# Headphone_Filter.net
KiCad netlist of a schematic drawn in Altium Designer
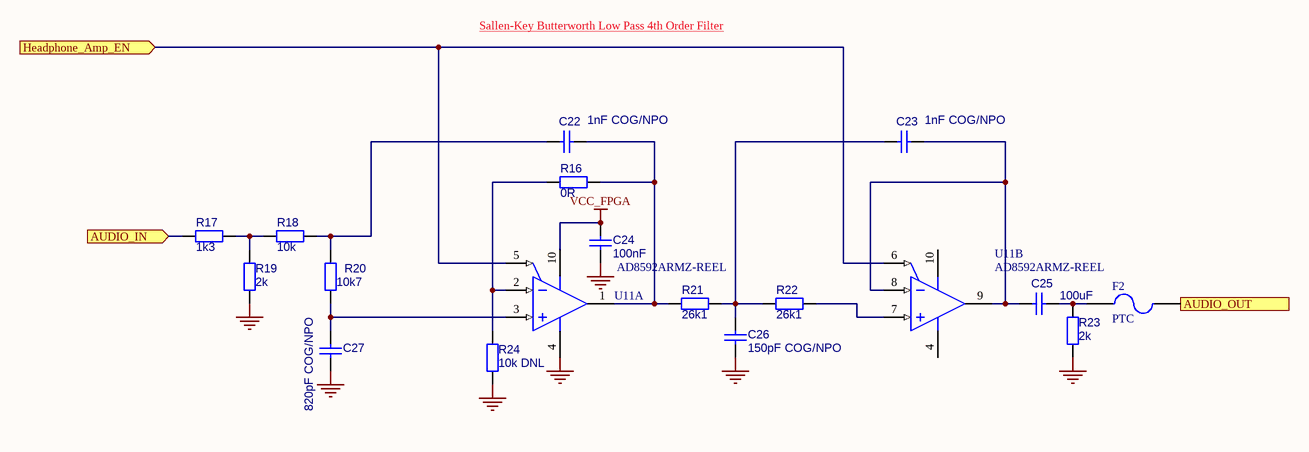
[diagram p0: Headphone Filter.SchDoc]

(export (version "E")
  (design (tool "Eeschema 10.0.6"))
  (components
    (comp (ref "C22")
      (value "1nF COG/NPO")
      (footprint "0603_CAP PF HD")
      (description "Capacitor")
      (fields (field (name "MANUFACTURER") "Wurth Electronics Inc."))
      (libsource (lib "Workshop Library 2010_06_24") (part "Cap"))
    )
    (comp (ref "C23")
      (value "1nF COG/NPO")
      (footprint "0603_CAP PF HD")
      (description "Capacitor")
      (fields (field (name "MANUFACTURER") "Wurth Electronics Inc."))
      (libsource (lib "Workshop Library 2010_06_24") (part "Cap"))
    )
    (comp (ref "C24")
      (value "100nF")
      (footprint "0603_CAP UF HD")
      (description "Capacitor")
      (libsource (lib "Workshop Library 2010_06_24") (part "Cap"))
    )
    (comp (ref "C25")
      (value "100uF")
      (footprint "1210-CAPACITOR UF")
      (description "Capacitor")
      (fields (field (name "MANUFACTURER") "Taiyo Yuden"))
      (libsource (lib "Workshop Library 2010_06_24") (part "Cap"))
    )
    (comp (ref "C26")
      (value "150pF COG/NPO")
      (footprint "0603_CAP PF HD")
      (description "Capacitor")
      (libsource (lib "Workshop Library 2010_06_24") (part "Cap"))
    )
    (comp (ref "C27")
      (value "820pF COG/NPO")
      (footprint "0603_CAP PF HD")
      (description "Capacitor")
      (libsource (lib "Workshop Library 2010_06_24") (part "Cap"))
    )
    (comp (ref "F2")
      (value "PTC")
      (footprint "0603-RESISTOR HD")
      (description "Fuse")
      (fields (field (name "MANUFACTURER") "Murata Electronics"))
      (libsource (lib "Workshop Library 2010_06_24") (part "Fuse"))
    )
    (comp (ref "R16")
      (value "0R")
      (footprint "0603-RESISTOR HD")
      (description "Resistor")
      (libsource (lib "") (part "Resistor_1"))
    )
    (comp (ref "R17")
      (value "1k3")
      (footprint "0603-RESISTOR HD")
      (description "Resistor")
      (libsource (lib "") (part "Resistor_1"))
    )
    (comp (ref "R18")
      (value "10k")
      (footprint "0603-RESISTOR HD")
      (description "Resistor")
      (libsource (lib "") (part "Resistor_2"))
    )
    (comp (ref "R19")
      (value "2k")
      (footprint "0603-RESISTOR HD")
      (description "Resistor")
      (libsource (lib "") (part "Resistor_3"))
    )
    (comp (ref "R20")
      (value "10k7")
      (footprint "0603-RESISTOR HD")
      (description "Resistor")
      (libsource (lib "Workshop Library 2010_06_24") (part "Resistor"))
    )
    (comp (ref "R21")
      (value "26k1")
      (footprint "0603-RESISTOR HD")
      (description "Resistor")
      (libsource (lib "") (part "Resistor_1"))
    )
    (comp (ref "R22")
      (value "26k1")
      (footprint "0603-RESISTOR HD")
      (description "Resistor")
      (libsource (lib "") (part "Resistor_2"))
    )
    (comp (ref "R23")
      (value "2k")
      (footprint "0603-RESISTOR HD")
      (description "Resistor")
      (libsource (lib "") (part "Resistor_3"))
    )
    (comp (ref "R24")
      (value "10k DNL")
      (footprint "0603-RESISTOR HD")
      (description "Resistor")
      (libsource (lib "") (part "Resistor_3"))
    )
    (comp (ref "U11")
      (value "AD8592ARMZ-REEL")
      (footprint "ADI-RM-10_M")
      (fields (field (name "MANUFACTURER") "Analog Devices"))
      (libsource (lib "Workshop Library 2010_06_24") (part "AD8592ARMZ-REEL"))
    )
  )
  (nets
    (net (code "1") (name "/AUDIO_IN") (class "Default")
      (node (ref "R17") (pin "2") (pinfunction "2_2") (pintype "passive"))
    )
    (net (code "2") (name "/AUDIO_OUT") (class "Default")
      (node (ref "F2") (pin "2") (pinfunction "2_2") (pintype "passive"))
    )
    (net (code "3") (name "/Headphone_Amp_EN") (class "Default")
      (node (ref "U11") (pin "5") (pinfunction "~{SDA}_5") (pintype "input"))
      (node (ref "U11") (pin "6") (pinfunction "~{SDB}_6") (pintype "input"))
    )
    (net (code "4") (name "GND") (class "Default")
      (node (ref "C24") (pin "2") (pinfunction "2_2") (pintype "passive"))
      (node (ref "C26") (pin "1") (pinfunction "1_1") (pintype "passive"))
      (node (ref "C27") (pin "2") (pinfunction "2_2") (pintype "passive"))
      (node (ref "R19") (pin "2") (pinfunction "2_2") (pintype "passive"))
      (node (ref "R23") (pin "2") (pinfunction "2_2") (pintype "passive"))
      (node (ref "R24") (pin "2") (pinfunction "2_2") (pintype "passive"))
      (node (ref "U11") (pin "4") (pinfunction "-V_4") (pintype "power_in"))
    )
    (net (code "5") (name "Net-(C22-Pad1)") (class "Default")
      (node (ref "C22") (pin "1") (pinfunction "1_1") (pintype "passive"))
      (node (ref "R18") (pin "2") (pinfunction "2_2") (pintype "passive"))
      (node (ref "R20") (pin "2") (pinfunction "2_2") (pintype "passive"))
    )
    (net (code "6") (name "Net-(C23-Pad1)") (class "Default")
      (node (ref "C23") (pin "1") (pinfunction "1_1") (pintype "passive"))
      (node (ref "C26") (pin "2") (pinfunction "2_2") (pintype "passive"))
      (node (ref "R21") (pin "1") (pinfunction "1_1") (pintype "passive"))
      (node (ref "R22") (pin "1") (pinfunction "1_1") (pintype "passive"))
    )
    (net (code "7") (name "Net-(C25-Pad2)") (class "Default")
      (node (ref "C25") (pin "2") (pinfunction "2_2") (pintype "passive"))
      (node (ref "F2") (pin "1") (pinfunction "1_1") (pintype "passive"))
      (node (ref "R23") (pin "1") (pinfunction "1_1") (pintype "passive"))
    )
    (net (code "8") (name "Net-(R17-Pad1)") (class "Default")
      (node (ref "R17") (pin "1") (pinfunction "1_1") (pintype "passive"))
      (node (ref "R18") (pin "1") (pinfunction "1_1") (pintype "passive"))
      (node (ref "R19") (pin "1") (pinfunction "1_1") (pintype "passive"))
    )
    (net (code "9") (name "Net-(U11A-+IN_A)") (class "Default")
      (node (ref "C27") (pin "1") (pinfunction "1_1") (pintype "passive"))
      (node (ref "R20") (pin "1") (pinfunction "1_1") (pintype "passive"))
      (node (ref "U11") (pin "3") (pinfunction "+IN_A_3") (pintype "input"))
    )
    (net (code "10") (name "Net-(U11A--IN_A)") (class "Default")
      (node (ref "R16") (pin "2") (pinfunction "2_2") (pintype "passive"))
      (node (ref "R24") (pin "1") (pinfunction "1_1") (pintype "passive"))
      (node (ref "U11") (pin "2") (pinfunction "-IN_A_2") (pintype "input"))
    )
    (net (code "11") (name "Net-(U11A-OUT_A)") (class "Default")
      (node (ref "C22") (pin "2") (pinfunction "2_2") (pintype "passive"))
      (node (ref "R16") (pin "1") (pinfunction "1_1") (pintype "passive"))
      (node (ref "R21") (pin "2") (pinfunction "2_2") (pintype "passive"))
      (node (ref "U11") (pin "1") (pinfunction "OUT_A_1") (pintype "tri_state"))
    )
    (net (code "12") (name "Net-(U11B-+IN_B)") (class "Default")
      (node (ref "R22") (pin "2") (pinfunction "2_2") (pintype "passive"))
      (node (ref "U11") (pin "7") (pinfunction "+IN_B_7") (pintype "input"))
    )
    (net (code "13") (name "Net-(U11B--IN_B)") (class "Default")
      (node (ref "C23") (pin "2") (pinfunction "2_2") (pintype "passive"))
      (node (ref "C25") (pin "1") (pinfunction "1_1") (pintype "passive"))
      (node (ref "U11") (pin "8") (pinfunction "-IN_B_8") (pintype "input"))
      (node (ref "U11") (pin "9") (pinfunction "OUT_B_9") (pintype "tri_state"))
    )
    (net (code "14") (name "VCC_FPGA") (class "Default")
      (node (ref "C24") (pin "1") (pinfunction "1_1") (pintype "passive"))
      (node (ref "U11") (pin "10") (pinfunction "+V_10") (pintype "power_in"))
    )
    (net (code "15") (name "unconnected-(U11B-+V-Pad10)") (class "Default")
      (node (ref "U11") (pin "10") (pinfunction "+V_10") (pintype "power_in"))
    )
    (net (code "16") (name "unconnected-(U11B--V-Pad4)") (class "Default")
      (node (ref "U11") (pin "4") (pinfunction "-V_4") (pintype "power_in"))
    )
  )
)
